# Lichtsensor.net
KiCad netlist of a schematic drawn in Altium Designer
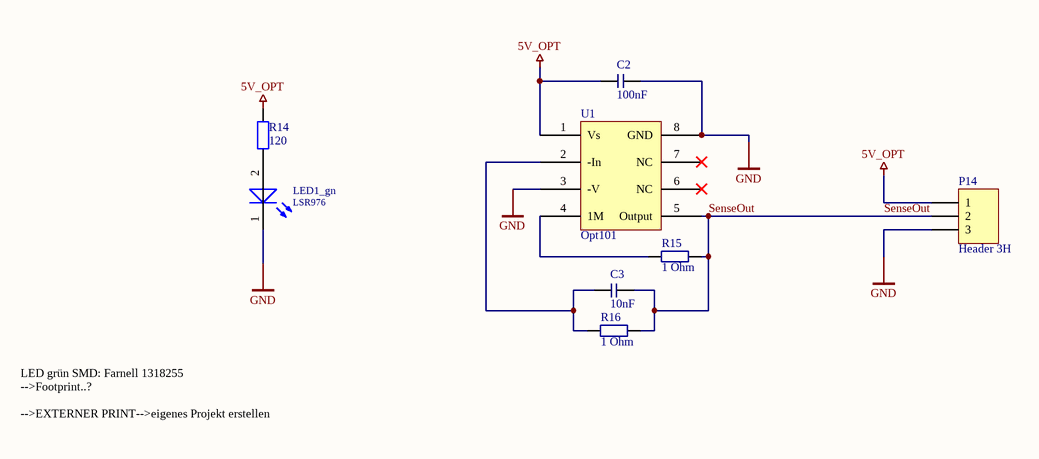
[diagram p0: Lichtsensor.SchDoc]

(export (version "E")
  (design (tool "Eeschema 10.0.6"))
  (components
    (comp (ref "C2")
      (value "100nF")
      (footprint "1206")
      (description "C1206")
      (libsource (lib "detektor_0") (part "C1206"))
    )
    (comp (ref "C3")
      (value "10nF")
      (footprint "1206")
      (description "C1206")
      (libsource (lib "detektor_0") (part "C1206"))
    )
    (comp (ref "LED1_gn")
      (value "LSR976")
      (footprint "GEN_LED0805_1K2A_2_H")
      (description "Hyper ChipLED, Red,")
      (fields (field (name "MANUFACTURER") "OSRAM") (field (name "PUBLISHER") "Stefan Ursella, M.Eng"))
      (libsource (lib "SysP2015") (part "OSR_LSR976_0805(1K2A)"))
    )
    (comp (ref "P14")
      (value "Header 3H")
      (footprint "HDR1X3H")
      (description "Header, 3-Pin, Right Angle")
      (fields (field (name "PUBLISHER") "Altium Limited"))
      (libsource (lib "Miscellaneous Connectors") (part "Header 3H"))
    )
    (comp (ref "R14")
      (value "120")
      (footprint "GEN_R0805_H")
      (description "generic resistor")
      (fields
        (field (name "MANUFACTURER") "Tbd")
        (field (name "Comment") "Generic")
        (field (name "PUBLISHER") "Altium Limited")
      )
      (libsource (lib "Motortreiber") (part "GEN_R_2"))
    )
    (comp (ref "R15")
      (value "1 Ohm")
      (footprint "1206")
      (description "R1206")
      (libsource (lib "detektor_0") (part "R1206"))
    )
    (comp (ref "R16")
      (value "1 Ohm")
      (footprint "1206")
      (description "R1206")
      (libsource (lib "detektor_0") (part "R1206"))
    )
    (comp (ref "U1") (value "Opt101") (footprint "Opt101") (libsource (lib "detektor_0") (part "Opt101")))
  )
  (nets
    (net (code "1") (name "/SenseOut") (class "Default")
      (node (ref "C3") (pin "2") (pinfunction "2_2") (pintype "passive"))
      (node (ref "P14") (pin "2") (pinfunction "2_2") (pintype "passive"))
      (node (ref "R15") (pin "2") (pinfunction "2_2") (pintype "passive"))
      (node (ref "R16") (pin "2") (pinfunction "2_2") (pintype "passive"))
      (node (ref "U1") (pin "5") (pinfunction "Output_5") (pintype "passive"))
    )
    (net (code "2") (name "5V_OPT") (class "Default")
      (node (ref "C2") (pin "1") (pinfunction "1_1") (pintype "passive"))
      (node (ref "P14") (pin "1") (pinfunction "1_1") (pintype "passive"))
      (node (ref "R14") (pin "2") (pinfunction "2_2") (pintype "passive"))
      (node (ref "U1") (pin "1") (pinfunction "Vs_1") (pintype "passive"))
    )
    (net (code "3") (name "GND") (class "Default")
      (node (ref "C2") (pin "2") (pinfunction "2_2") (pintype "passive"))
      (node (ref "LED1_gn") (pin "1") (pinfunction "K_1") (pintype "passive"))
      (node (ref "P14") (pin "3") (pinfunction "3_3") (pintype "passive"))
      (node (ref "U1") (pin "3") (pinfunction "-V_3") (pintype "passive"))
      (node (ref "U1") (pin "8") (pinfunction "GND_8") (pintype "passive"))
    )
    (net (code "4") (name "Net-(LED1_gn-A)") (class "Default")
      (node (ref "LED1_gn") (pin "2") (pinfunction "A_2") (pintype "passive"))
      (node (ref "R14") (pin "1") (pinfunction "1_1") (pintype "passive"))
    )
    (net (code "5") (name "Net-(U1--In)") (class "Default")
      (node (ref "C3") (pin "1") (pinfunction "1_1") (pintype "passive"))
      (node (ref "R16") (pin "1") (pinfunction "1_1") (pintype "passive"))
      (node (ref "U1") (pin "2") (pinfunction "-In_2") (pintype "passive"))
    )
    (net (code "6") (name "Net-(U1-1M)") (class "Default")
      (node (ref "R15") (pin "1") (pinfunction "1_1") (pintype "passive"))
      (node (ref "U1") (pin "4") (pinfunction "1M_4") (pintype "passive"))
    )
    (net (code "7") (name "unconnected-(U1-NC-Pad6)") (class "Default")
      (node (ref "U1") (pin "6") (pinfunction "NC_6") (pintype "passive+no_connect"))
    )
    (net (code "8") (name "unconnected-(U1-NC-Pad7)") (class "Default")
      (node (ref "U1") (pin "7") (pinfunction "NC_7") (pintype "passive+no_connect"))
    )
  )
)
